# RPi_TSOP.net
KiCad netlist of a schematic drawn in Altium Designer
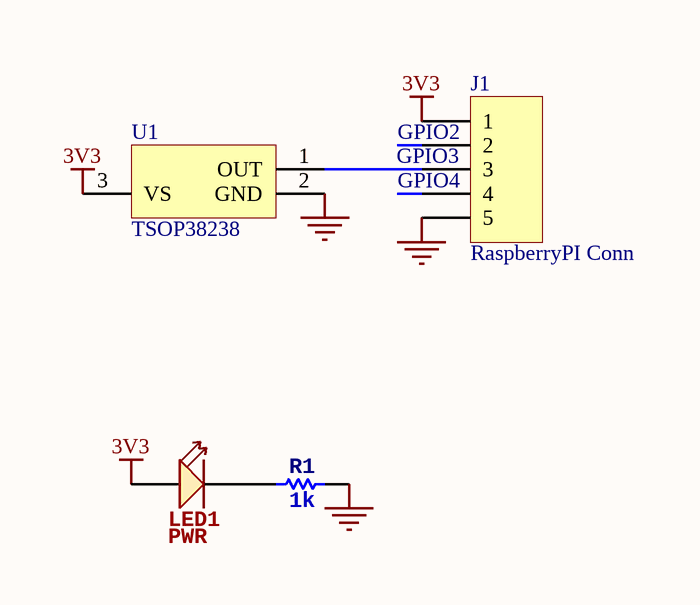
[diagram p0: RPi_TSOP.SchDoc]

(export (version "E")
  (design (tool "Eeschema 10.0.6"))
  (components
    (comp (ref "J1")
      (value "RaspberryPI Conn")
      (footprint "HDR1X5")
      (description "Header, 5-Pin")
      (fields (field (name "PUBLISHER") "Altium Limited"))
      (libsource (lib "Miscellaneous Connectors") (part "Header 5"))
    )
    (comp (ref "LED1")
      (value "PWR")
      (footprint "LED-0805")
      (description "5V Power Indicator")
      (fields (field (name "MPN") "17-215SURC/S530-A2/TR8"))
      (libsource (lib "105848") (part "SMD-LED-CLEAR-RED(0805)"))
    )
    (comp (ref "R1")
      (value "1k")
      (footprint "RESC1206(3216)_M")
      (description "RESISTOR, SMD, 1206")
      (fields (field (name "TOLERANCE") "5%") (field (name "Comment") "Resistor"))
      (libsource (lib "altium-import") (part "root_0_CMP-2003-01077-1_"))
    )
    (comp (ref "U1")
      (value "TSOP38238")
      (footprint "VISH-TSOP38238")
      (description "IR Receiver Modules for Remote Control System, 2.5 to 5.5 V, -25 to 85 degC, 3-Pin THD, RoHS, Bulk")
      (fields (field (name "TOLERANCE") "30ppm"))
      (libsource (lib "TSOP") (part "CMP-1666-00022-1"))
    )
  )
  (nets
    (net (code "1") (name "/GPIO2") (class "Default")
      (node (ref "J1") (pin "2") (pinfunction "2_2") (pintype "passive"))
    )
    (net (code "2") (name "/GPIO3") (class "Default")
      (node (ref "J1") (pin "3") (pinfunction "3_3") (pintype "passive"))
      (node (ref "U1") (pin "1") (pinfunction "OUT_1") (pintype "power_in"))
    )
    (net (code "3") (name "/GPIO4") (class "Default")
      (node (ref "J1") (pin "4") (pinfunction "4_4") (pintype "passive"))
    )
    (net (code "4") (name "3V3") (class "Default")
      (node (ref "J1") (pin "1") (pinfunction "1_1") (pintype "passive"))
      (node (ref "LED1") (pin "+") (pinfunction "+_+") (pintype "passive"))
      (node (ref "U1") (pin "3") (pinfunction "VS_3") (pintype "power_in"))
    )
    (net (code "5") (name "GND") (class "Default")
      (node (ref "J1") (pin "5") (pinfunction "5_5") (pintype "passive"))
      (node (ref "R1") (pin "2") (pinfunction "2_2") (pintype "passive"))
      (node (ref "U1") (pin "2") (pinfunction "GND_2") (pintype "power_in"))
    )
    (net (code "6") (name "Net-(LED1-Pad-)") (class "Default")
      (node (ref "LED1") (pin "-") (pinfunction "-_-") (pintype "passive"))
      (node (ref "R1") (pin "1") (pinfunction "1_1") (pintype "passive"))
    )
  )
)
